# product.net
KiCad netlist of a schematic drawn in EAGLE
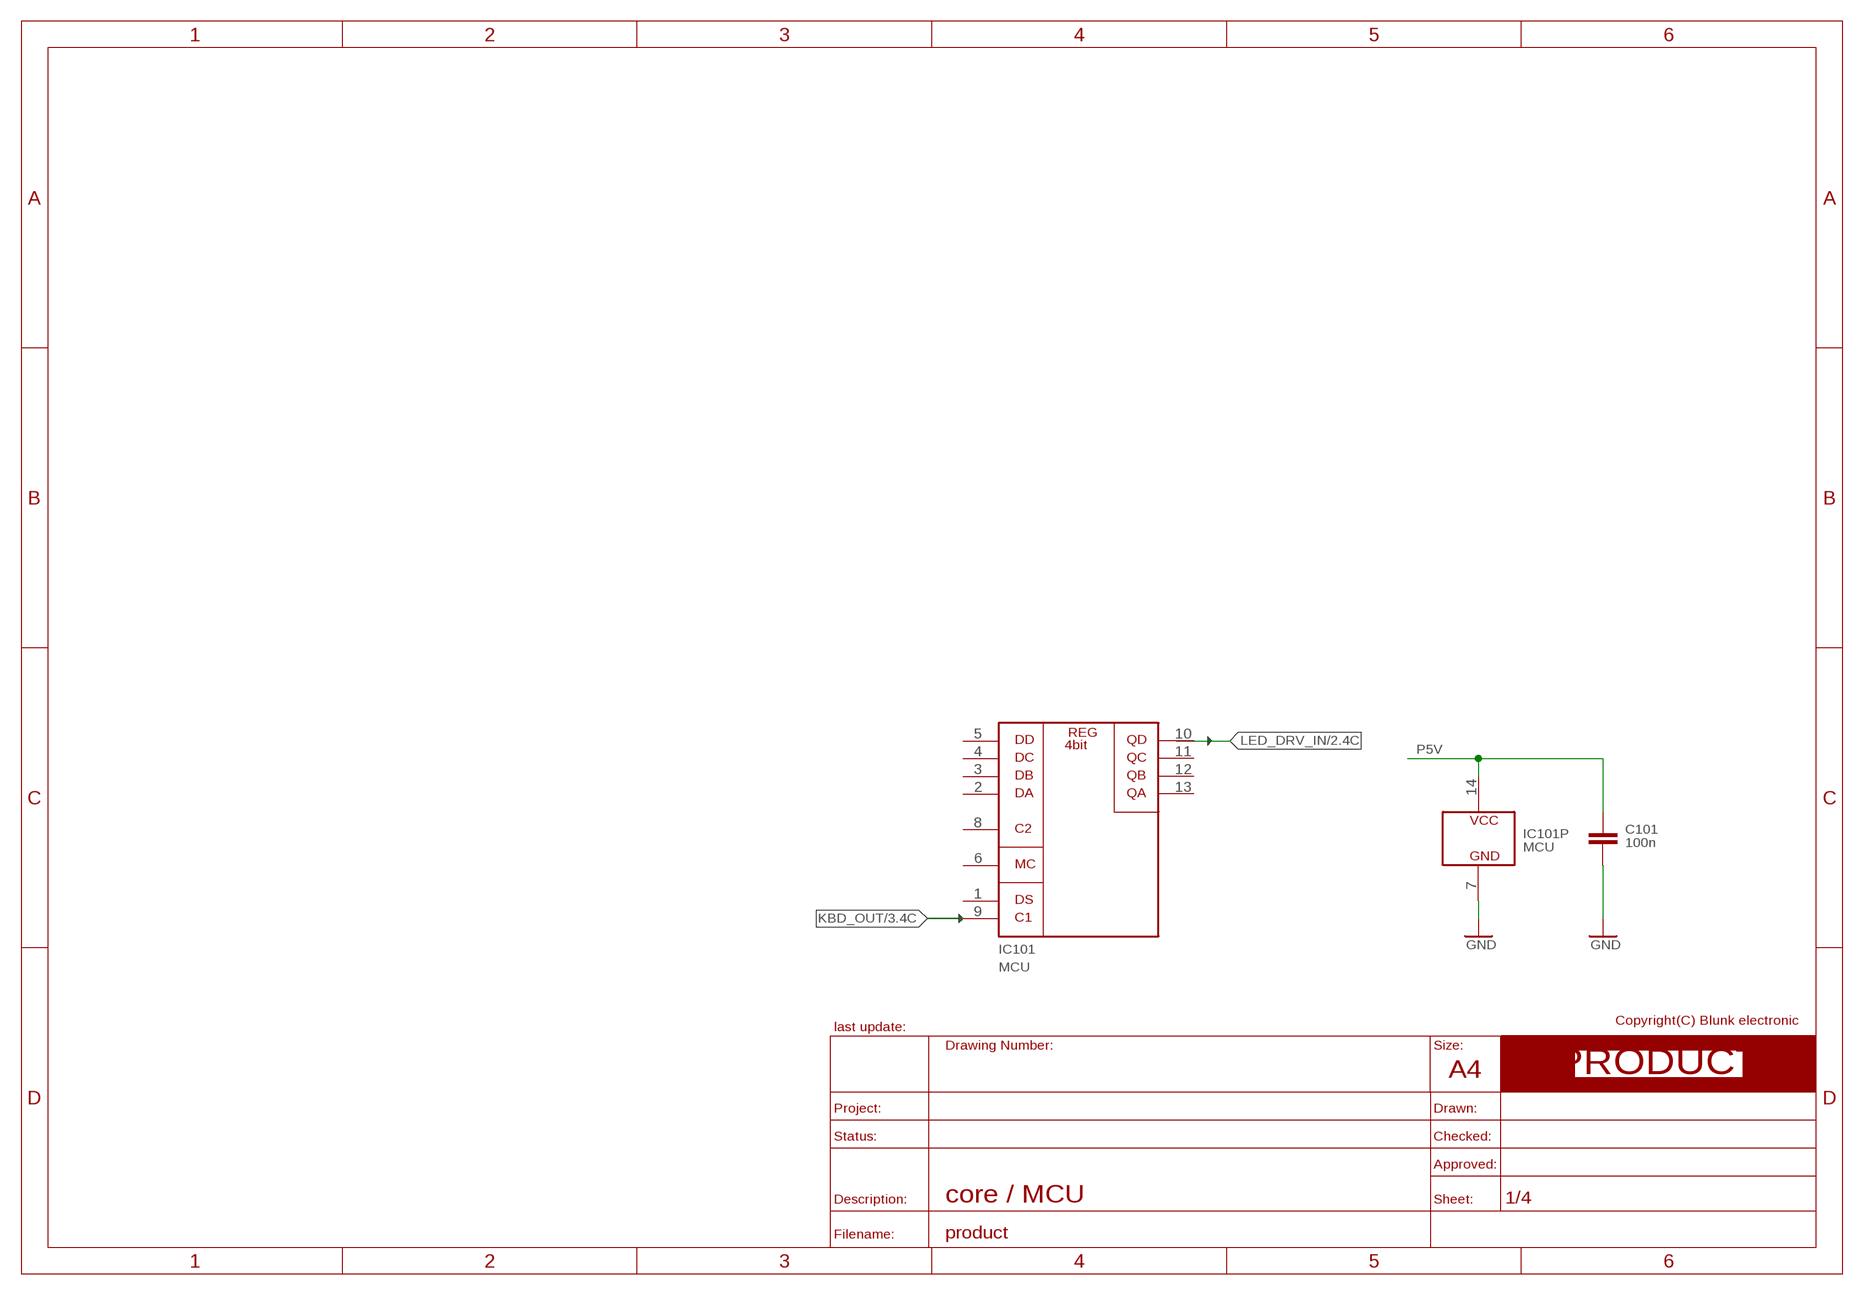
[diagram p0: schematic, sheet 1]
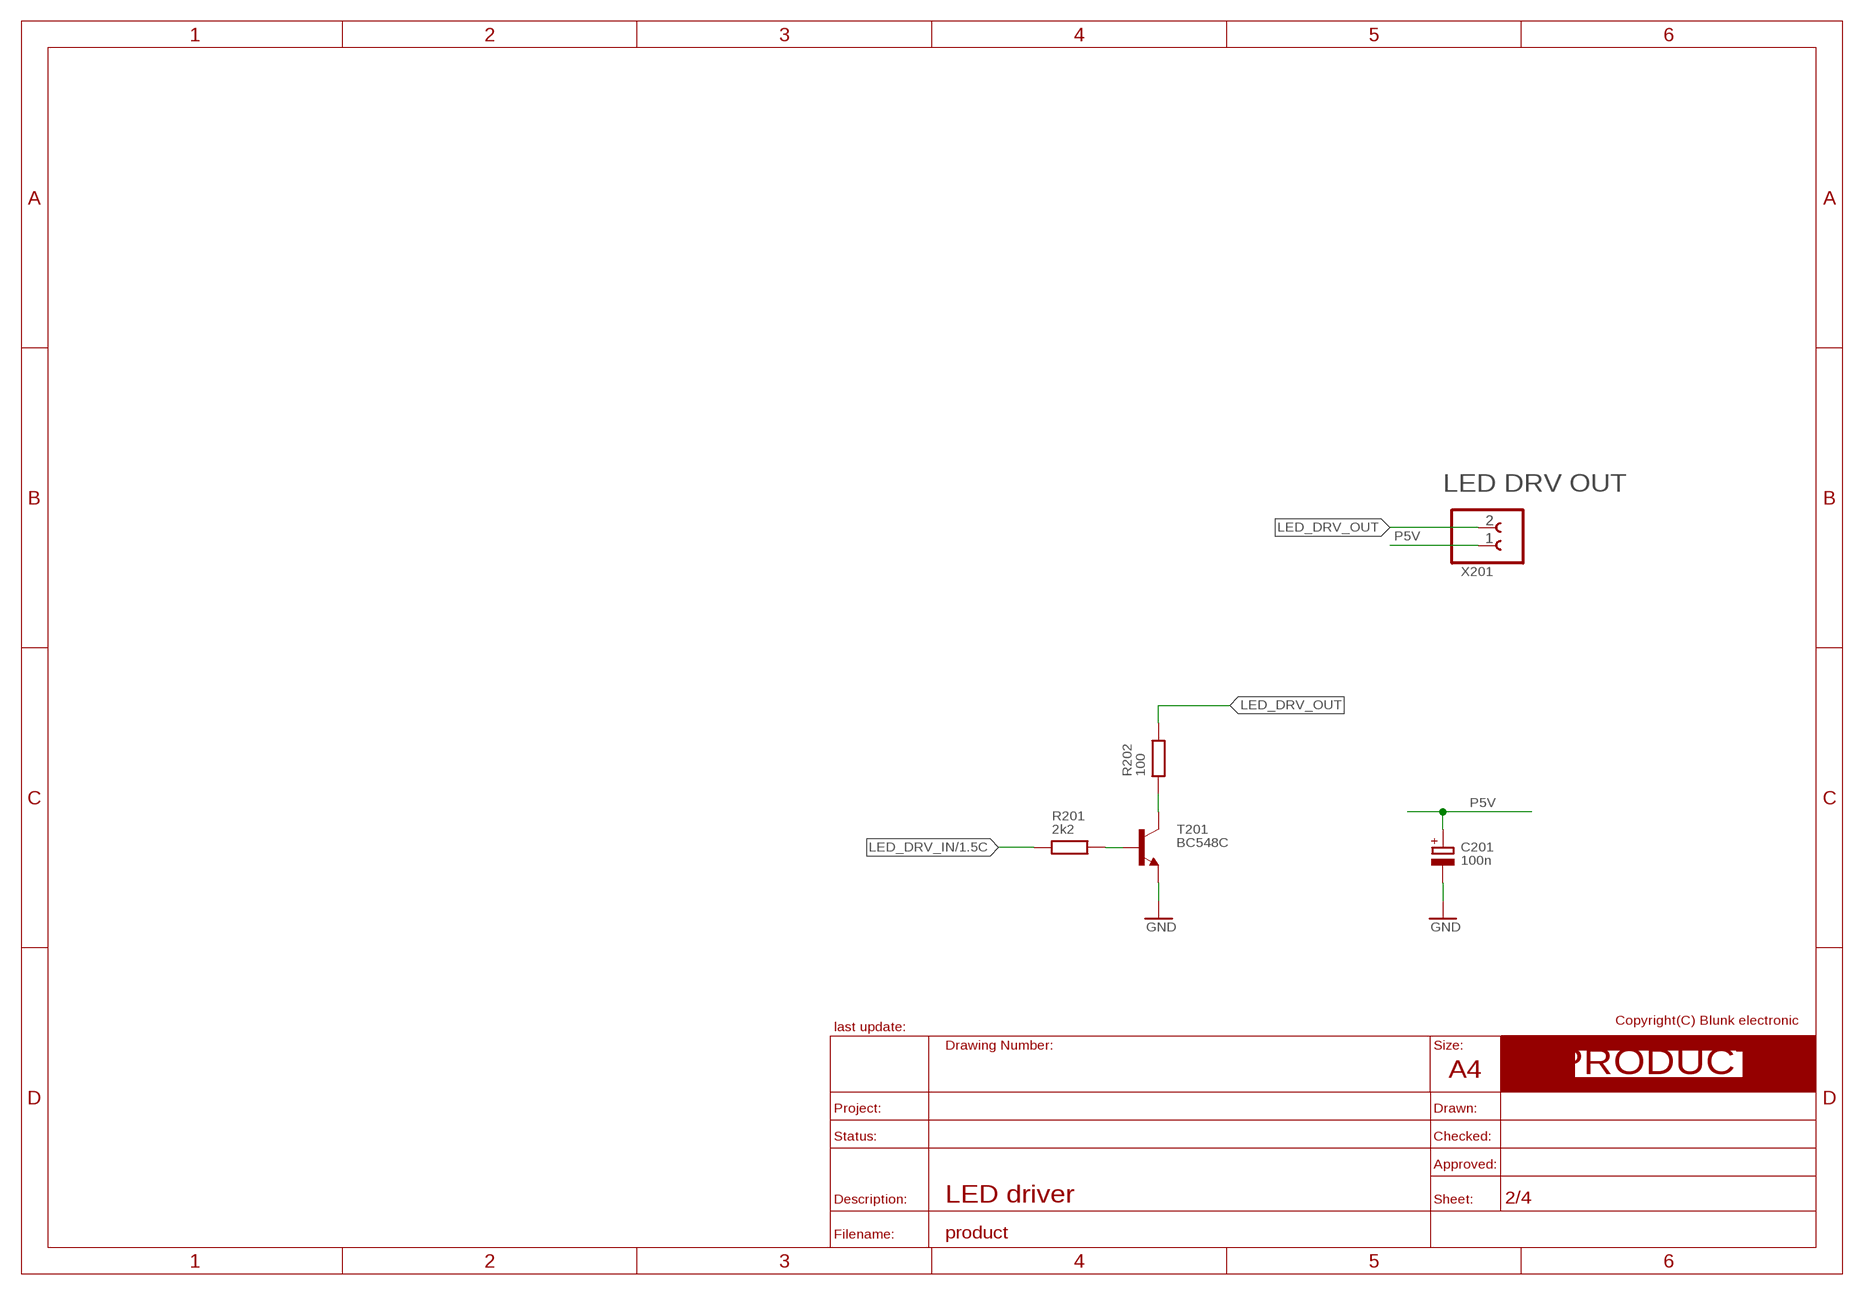
[diagram p1: schematic, sheet 2]
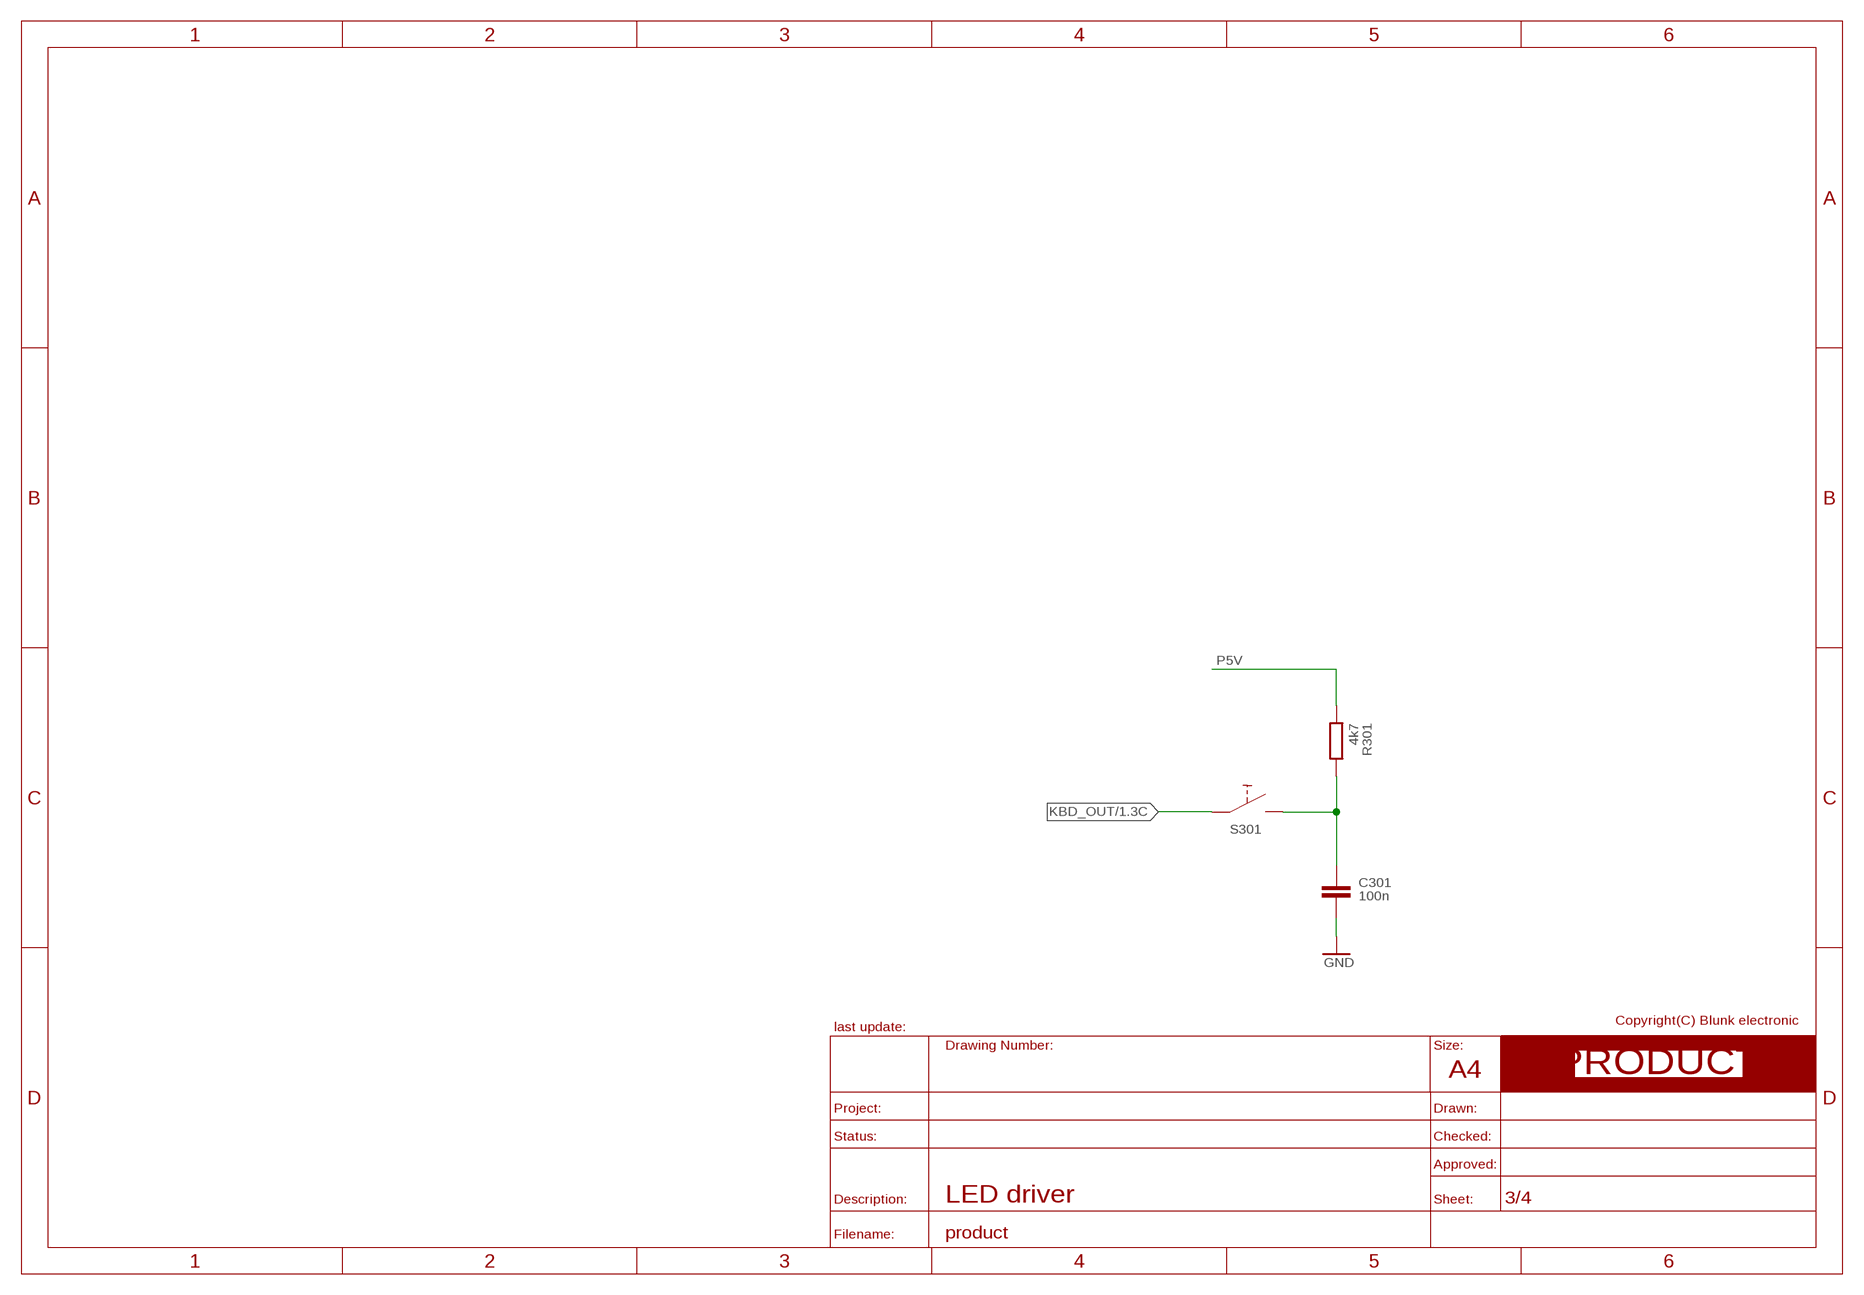
[diagram p2: schematic, sheet 3]
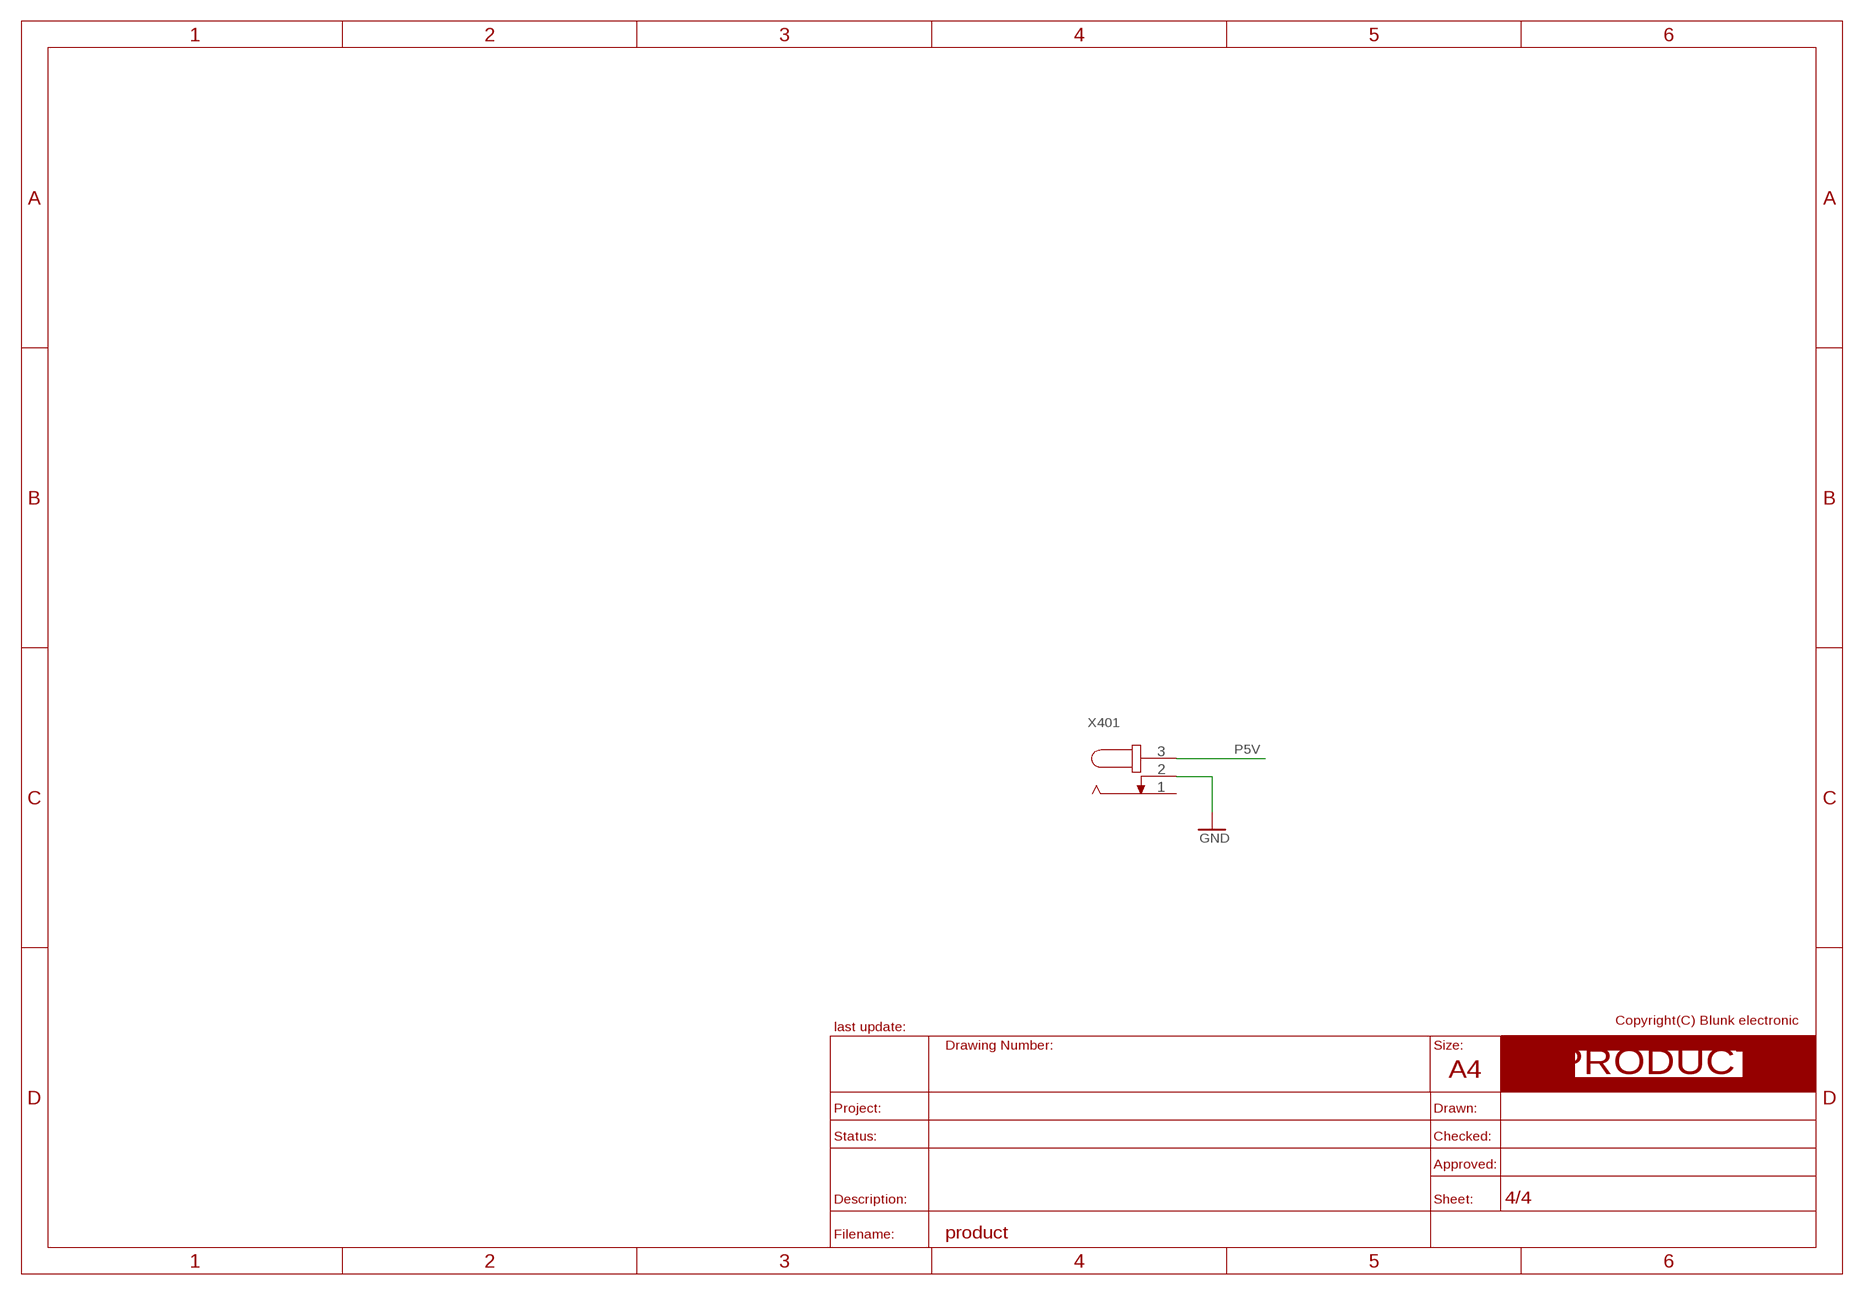
[diagram p3: schematic, sheet 4]

(export (version "E")
  (design (tool "Eeschema 10.0.6"))
  (components
    (comp (ref "C101")
      (value "100n")
      (footprint "eagle-import:S_0805")
      (libsource (lib "eagle-import") (part "C_S_0805"))
    )
    (comp (ref "IC101")
      (value "MCU")
      (footprint "eagle-import:S_SO14")
      (libsource (lib "eagle-import") (part "7495D"))
    )
    (comp (ref "X401")
      (value "POWER_JACK-T-0")
      (footprint "eagle-import:T_POWER_JACK_SPC4077")
      (libsource (lib "eagle-import") (part "POWER_JACK-T-0"))
    )
    (comp (ref "C201")
      (value "100n")
      (footprint "eagle-import:S_6032")
      (libsource (lib "eagle-import") (part "C_POL_S_6032"))
    )
    (comp (ref "R201")
      (value "2k2")
      (footprint "eagle-import:S_0805")
      (libsource (lib "eagle-import") (part "R_S_0805"))
    )
    (comp (ref "R202")
      (value "100")
      (footprint "eagle-import:S_0805")
      (libsource (lib "eagle-import") (part "R_S_0805"))
    )
    (comp (ref "T201")
      (value "BC548C")
      (footprint "eagle-import:S_SOT23")
      (libsource (lib "eagle-import") (part "NPN_S_SOT23"))
    )
    (comp (ref "X201")
      (value "CLAMP_1X2-T-2.5MM")
      (footprint "eagle-import:T_WIRE_CLAMP_1X2_PITCH_2MM5")
      (fields (field (name "FUNCTION") "LED DRV OUT"))
      (libsource (lib "eagle-import") (part "CLAMP_1X2-T-2.5MM"))
    )
    (comp (ref "C301")
      (value "100n")
      (footprint "eagle-import:S_0805")
      (libsource (lib "eagle-import") (part "C_S_0805"))
    )
    (comp (ref "R301")
      (value "4k7")
      (footprint "eagle-import:S_0805")
      (libsource (lib "eagle-import") (part "R_S_0805"))
    )
    (comp (ref "S301")
      (value "PUSH_BUTTON_S_6X6MM")
      (footprint "eagle-import:S_PUSH_BUTTON_6X6")
      (libsource (lib "eagle-import") (part "PUSH_BUTTON_S_6X6MM"))
    )
  )
  (nets
    (net (code "1") (name "GND") (class "Default")
      (node (ref "C101") (pin "2") (pinfunction "2_2") (pintype "passive"))
      (node (ref "C201") (pin "-") (pinfunction "-_-") (pintype "passive"))
      (node (ref "C301") (pin "2") (pinfunction "2_2") (pintype "passive"))
      (node (ref "IC101") (pin "7") (pinfunction "GND_7") (pintype "power_in"))
      (node (ref "T201") (pin "2") (pinfunction "E_2") (pintype "passive"))
      (node (ref "X401") (pin "2") (pinfunction "2_2") (pintype "passive"))
    )
    (net (code "2") (name "KBD_OUT") (class "Default")
      (node (ref "IC101") (pin "9") (pinfunction "C1_9") (pintype "input"))
      (node (ref "S301") (pin "A") (pinfunction "A1_A") (pintype "passive"))
      (node (ref "S301") (pin "A1") (pinfunction "A1_A1") (pintype "passive"))
    )
    (net (code "3") (name "LED_DRV_IN") (class "Default")
      (node (ref "IC101") (pin "10") (pinfunction "QD_10") (pintype "output"))
      (node (ref "R201") (pin "1") (pinfunction "1_1") (pintype "passive"))
    )
    (net (code "4") (name "LED_DRV_OUT") (class "Default")
      (node (ref "R202") (pin "2") (pinfunction "2_2") (pintype "passive"))
      (node (ref "X201") (pin "2") (pinfunction "2_2") (pintype "passive"))
    )
    (net (code "5") (name "Net-(C301-Pad1)") (class "Default")
      (node (ref "C301") (pin "1") (pinfunction "1_1") (pintype "passive"))
      (node (ref "R301") (pin "2") (pinfunction "2_2") (pintype "passive"))
      (node (ref "S301") (pin "B") (pinfunction "B1_B") (pintype "passive"))
      (node (ref "S301") (pin "B1") (pinfunction "B1_B1") (pintype "passive"))
    )
    (net (code "6") (name "Net-(T201-B)") (class "Default")
      (node (ref "R201") (pin "2") (pinfunction "2_2") (pintype "passive"))
      (node (ref "T201") (pin "1") (pinfunction "B_1") (pintype "passive"))
    )
    (net (code "7") (name "Net-(T201-C)") (class "Default")
      (node (ref "R202") (pin "1") (pinfunction "1_1") (pintype "passive"))
      (node (ref "T201") (pin "3") (pinfunction "C_3") (pintype "passive"))
    )
    (net (code "8") (name "P5V") (class "Default")
      (node (ref "C101") (pin "1") (pinfunction "1_1") (pintype "passive"))
      (node (ref "C201") (pin "+") (pinfunction "+_+") (pintype "passive"))
      (node (ref "IC101") (pin "14") (pinfunction "VCC_14") (pintype "power_in"))
      (node (ref "R301") (pin "1") (pinfunction "1_1") (pintype "passive"))
      (node (ref "X201") (pin "1") (pinfunction "1_1") (pintype "passive"))
      (node (ref "X401") (pin "3") (pinfunction "3_3") (pintype "passive"))
    )
    (net (code "9") (name "unconnected-(IC101A-C2-Pad8)") (class "Default")
      (node (ref "IC101") (pin "8") (pinfunction "C2_8") (pintype "input"))
    )
    (net (code "10") (name "unconnected-(IC101A-DA-Pad2)") (class "Default")
      (node (ref "IC101") (pin "2") (pinfunction "DA_2") (pintype "input"))
    )
    (net (code "11") (name "unconnected-(IC101A-DB-Pad3)") (class "Default")
      (node (ref "IC101") (pin "3") (pinfunction "DB_3") (pintype "input"))
    )
    (net (code "12") (name "unconnected-(IC101A-DC-Pad4)") (class "Default")
      (node (ref "IC101") (pin "4") (pinfunction "DC_4") (pintype "input"))
    )
    (net (code "13") (name "unconnected-(IC101A-DD-Pad5)") (class "Default")
      (node (ref "IC101") (pin "5") (pinfunction "DD_5") (pintype "input"))
    )
    (net (code "14") (name "unconnected-(IC101A-DS-Pad1)") (class "Default")
      (node (ref "IC101") (pin "1") (pinfunction "DS_1") (pintype "input"))
    )
    (net (code "15") (name "unconnected-(IC101A-MC-Pad6)") (class "Default")
      (node (ref "IC101") (pin "6") (pinfunction "MC_6") (pintype "input"))
    )
    (net (code "16") (name "unconnected-(IC101A-QA-Pad13)") (class "Default")
      (node (ref "IC101") (pin "13") (pinfunction "QA_13") (pintype "output"))
    )
    (net (code "17") (name "unconnected-(IC101A-QB-Pad12)") (class "Default")
      (node (ref "IC101") (pin "12") (pinfunction "QB_12") (pintype "output"))
    )
    (net (code "18") (name "unconnected-(IC101A-QC-Pad11)") (class "Default")
      (node (ref "IC101") (pin "11") (pinfunction "QC_11") (pintype "output"))
    )
    (net (code "19") (name "unconnected-(X401-Pad1)") (class "Default")
      (node (ref "X401") (pin "1") (pinfunction "1_1") (pintype "passive"))
    )
  )
)
